# SM_Balam_22.net
KiCad netlist of a schematic drawn in Altium Designer
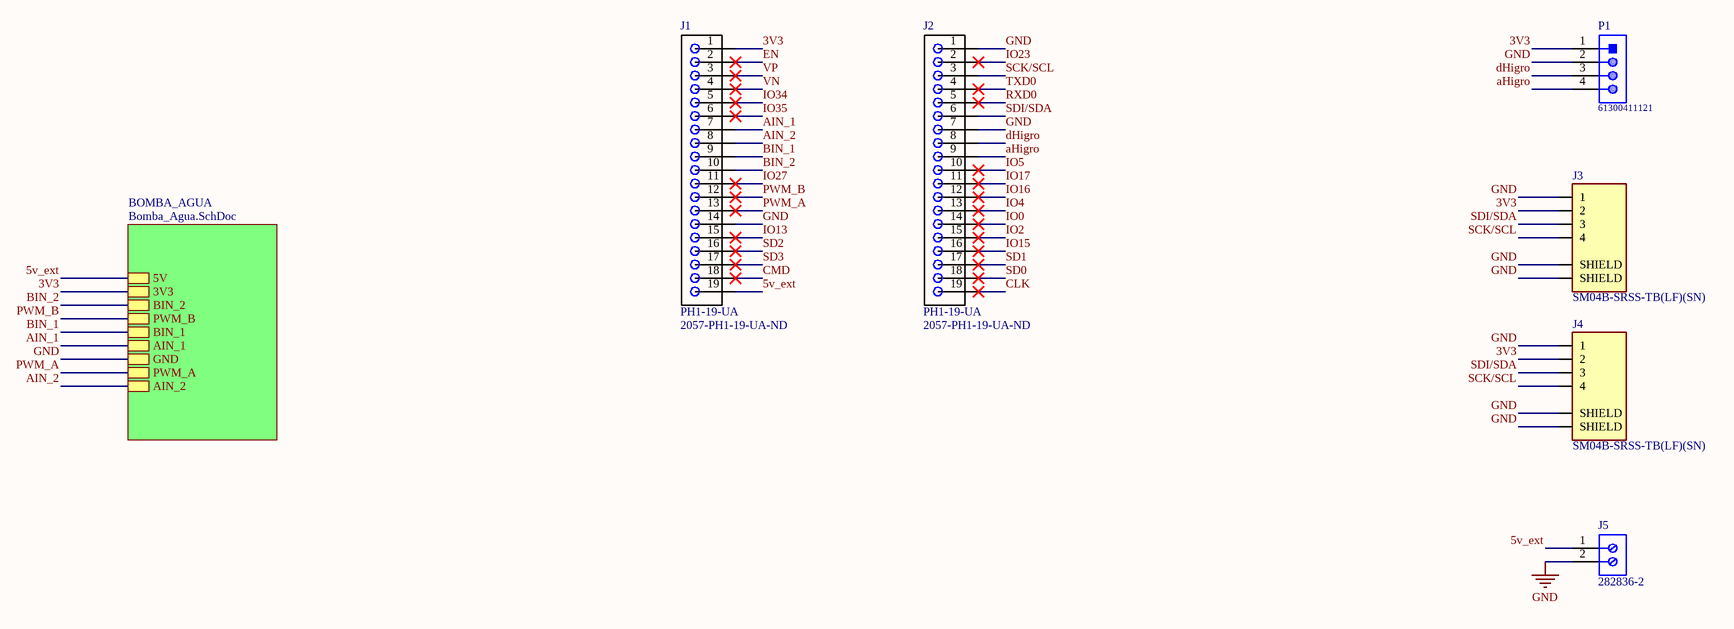
[diagram p0: SM_Balam_22.SchDoc]

(export (version "E")
  (design (tool "Eeschema 10.0.6"))
  (components
    (comp (ref "J1")
      (value "PH1-19-UA")
      (footprint "PH1-19-UA - Socket")
      (description "Connector Header Through Hole 19 position 0.100\" (2.54mm)")
      (fields (field (name "SUPPLIER PART NUMBER 1") "2057-PH1-19-UA-ND"))
      (libsource (lib "Isidro_Library") (part "PH1-19-UA"))
    )
    (comp (ref "J2")
      (value "PH1-19-UA")
      (footprint "PH1-19-UA - Socket")
      (description "Connector Header Through Hole 19 position 0.100\" (2.54mm)")
      (fields (field (name "SUPPLIER PART NUMBER 1") "2057-PH1-19-UA-ND"))
      (libsource (lib "Isidro_Library") (part "PH1-19-UA"))
    )
    (comp (ref "J3")
      (value "SM04B-SRSS-TB(LF)(SN)")
      (footprint "JST_SM04B-SRSS-TB(LF)(SN)")
      (description "Connector Header Surface Mount, Right Angle 4 position 0.039 _1.00mm_")
      (fields (field (name "MF") "JST Sales") (field (name "MP") "SM04B-SRSS-TB_LF__SN_"))
      (libsource (lib "AQIMon") (part "SM04B-SRSS-TB(LF)(SN)"))
    )
    (comp (ref "J4")
      (value "SM04B-SRSS-TB(LF)(SN)")
      (footprint "JST_SM04B-SRSS-TB(LF)(SN)")
      (description "Connector Header Surface Mount, Right Angle 4 position 0.039 _1.00mm_")
      (fields (field (name "MF") "JST Sales") (field (name "MP") "SM04B-SRSS-TB_LF__SN_"))
      (libsource (lib "AQIMon") (part "SM04B-SRSS-TB(LF)(SN)"))
    )
    (comp (ref "J5")
      (value "282836-2")
      (footprint "TECO-282836-2_V")
      (description "Female Header, Pitch 5 mm, 1 x 2 Position, Height 10 mm, Tail Length 3.5 mm, Rohs, Bulk")
      (fields (field (name "VOLTAGE") "300V") (field (name "MANUFACTURER") "TE Connectivity"))
      (libsource (lib "Altium Content Vault") (part "CN-1P-F-TB2"))
    )
    (comp (ref "P1")
      (value "61300411121")
      (footprint "61300411121")
      (description "THT Vertical Pin Header WR-PHD, Pitch 2.54 mm, Single Row, 4 pins")
      (fields (field (name "MANUFACTURER") "Wurth Elektronik") (field (name "PUBLISHER") "WurthElektronik"))
      (libsource (lib "Altium Content Vault") (part "WE-CN-1P-M-R4"))
    )
  )
  (nets
    (net (code "1") (name "/3V3") (class "Default")
      (node (ref "J1") (pin "1") (pinfunction "1_1") (pintype "passive"))
      (node (ref "J3") (pin "2") (pinfunction "2_2") (pintype "passive"))
      (node (ref "J4") (pin "2") (pinfunction "2_2") (pintype "passive"))
      (node (ref "P1") (pin "1") (pinfunction "1_1") (pintype "passive"))
    )
    (net (code "2") (name "/5v_ext") (class "Default")
      (node (ref "J1") (pin "19") (pinfunction "19_19") (pintype "passive"))
      (node (ref "J5") (pin "1") (pinfunction "1_1") (pintype "passive"))
    )
    (net (code "3") (name "/AIN_1") (class "Default")
      (node (ref "J1") (pin "7") (pinfunction "7_7") (pintype "passive"))
    )
    (net (code "4") (name "/AIN_2") (class "Default")
      (node (ref "J1") (pin "8") (pinfunction "8_8") (pintype "passive"))
    )
    (net (code "5") (name "/BIN_1") (class "Default")
      (node (ref "J1") (pin "9") (pinfunction "9_9") (pintype "passive"))
    )
    (net (code "6") (name "/BIN_2") (class "Default")
      (node (ref "J1") (pin "10") (pinfunction "10_10") (pintype "passive"))
    )
    (net (code "7") (name "/CLK") (class "Default")
      (node (ref "J2") (pin "19") (pinfunction "19_19") (pintype "passive+no_connect"))
    )
    (net (code "8") (name "/CMD") (class "Default")
      (node (ref "J1") (pin "18") (pinfunction "18_18") (pintype "passive+no_connect"))
    )
    (net (code "9") (name "/EN") (class "Default")
      (node (ref "J1") (pin "2") (pinfunction "2_2") (pintype "passive+no_connect"))
    )
    (net (code "10") (name "/IO0") (class "Default")
      (node (ref "J2") (pin "14") (pinfunction "14_14") (pintype "passive+no_connect"))
    )
    (net (code "11") (name "/IO2") (class "Default")
      (node (ref "J2") (pin "15") (pinfunction "15_15") (pintype "passive+no_connect"))
    )
    (net (code "12") (name "/IO4") (class "Default")
      (node (ref "J2") (pin "13") (pinfunction "13_13") (pintype "passive+no_connect"))
    )
    (net (code "13") (name "/IO5") (class "Default")
      (node (ref "J2") (pin "10") (pinfunction "10_10") (pintype "passive+no_connect"))
    )
    (net (code "14") (name "/IO13") (class "Default")
      (node (ref "J1") (pin "15") (pinfunction "15_15") (pintype "passive+no_connect"))
    )
    (net (code "15") (name "/IO15") (class "Default")
      (node (ref "J2") (pin "16") (pinfunction "16_16") (pintype "passive+no_connect"))
    )
    (net (code "16") (name "/IO16") (class "Default")
      (node (ref "J2") (pin "12") (pinfunction "12_12") (pintype "passive+no_connect"))
    )
    (net (code "17") (name "/IO17") (class "Default")
      (node (ref "J2") (pin "11") (pinfunction "11_11") (pintype "passive+no_connect"))
    )
    (net (code "18") (name "/IO23") (class "Default")
      (node (ref "J2") (pin "2") (pinfunction "2_2") (pintype "passive+no_connect"))
    )
    (net (code "19") (name "/IO27") (class "Default")
      (node (ref "J1") (pin "11") (pinfunction "11_11") (pintype "passive+no_connect"))
    )
    (net (code "20") (name "/IO34") (class "Default")
      (node (ref "J1") (pin "5") (pinfunction "5_5") (pintype "passive+no_connect"))
    )
    (net (code "21") (name "/IO35") (class "Default")
      (node (ref "J1") (pin "6") (pinfunction "6_6") (pintype "passive+no_connect"))
    )
    (net (code "22") (name "/PWM_A") (class "Default")
      (node (ref "J1") (pin "13") (pinfunction "13_13") (pintype "passive+no_connect"))
    )
    (net (code "23") (name "/PWM_B") (class "Default")
      (node (ref "J1") (pin "12") (pinfunction "12_12") (pintype "passive+no_connect"))
    )
    (net (code "24") (name "/RXD0") (class "Default")
      (node (ref "J2") (pin "5") (pinfunction "5_5") (pintype "passive+no_connect"))
    )
    (net (code "25") (name "/SCK{slash}SCL") (class "Default")
      (node (ref "J2") (pin "3") (pinfunction "3_3") (pintype "passive"))
      (node (ref "J3") (pin "4") (pinfunction "4_4") (pintype "passive"))
      (node (ref "J4") (pin "4") (pinfunction "4_4") (pintype "passive"))
    )
    (net (code "26") (name "/SD0") (class "Default")
      (node (ref "J2") (pin "18") (pinfunction "18_18") (pintype "passive+no_connect"))
    )
    (net (code "27") (name "/SD1") (class "Default")
      (node (ref "J2") (pin "17") (pinfunction "17_17") (pintype "passive+no_connect"))
    )
    (net (code "28") (name "/SD2") (class "Default")
      (node (ref "J1") (pin "16") (pinfunction "16_16") (pintype "passive+no_connect"))
    )
    (net (code "29") (name "/SD3") (class "Default")
      (node (ref "J1") (pin "17") (pinfunction "17_17") (pintype "passive+no_connect"))
    )
    (net (code "30") (name "/SDI{slash}SDA") (class "Default")
      (node (ref "J2") (pin "6") (pinfunction "6_6") (pintype "passive"))
      (node (ref "J3") (pin "3") (pinfunction "3_3") (pintype "passive"))
      (node (ref "J4") (pin "3") (pinfunction "3_3") (pintype "passive"))
    )
    (net (code "31") (name "/TXD0") (class "Default")
      (node (ref "J2") (pin "4") (pinfunction "4_4") (pintype "passive+no_connect"))
    )
    (net (code "32") (name "/VN") (class "Default")
      (node (ref "J1") (pin "4") (pinfunction "4_4") (pintype "passive+no_connect"))
    )
    (net (code "33") (name "/VP") (class "Default")
      (node (ref "J1") (pin "3") (pinfunction "3_3") (pintype "passive+no_connect"))
    )
    (net (code "34") (name "/aHigro") (class "Default")
      (node (ref "J2") (pin "9") (pinfunction "9_9") (pintype "passive"))
      (node (ref "P1") (pin "4") (pinfunction "4_4") (pintype "passive"))
    )
    (net (code "35") (name "/dHigro") (class "Default")
      (node (ref "J2") (pin "8") (pinfunction "8_8") (pintype "passive"))
      (node (ref "P1") (pin "3") (pinfunction "3_3") (pintype "passive"))
    )
    (net (code "36") (name "GND") (class "Default")
      (node (ref "J1") (pin "14") (pinfunction "14_14") (pintype "passive"))
      (node (ref "J2") (pin "1") (pinfunction "1_1") (pintype "passive"))
      (node (ref "J2") (pin "7") (pinfunction "7_7") (pintype "passive"))
      (node (ref "J3") (pin "1") (pinfunction "1_1") (pintype "passive"))
      (node (ref "J3") (pin "S1") (pinfunction "SHIELD_S1") (pintype "passive"))
      (node (ref "J3") (pin "S2") (pinfunction "SHIELD_S2") (pintype "passive"))
      (node (ref "J4") (pin "1") (pinfunction "1_1") (pintype "passive"))
      (node (ref "J4") (pin "S1") (pinfunction "SHIELD_S1") (pintype "passive"))
      (node (ref "J4") (pin "S2") (pinfunction "SHIELD_S2") (pintype "passive"))
      (node (ref "J5") (pin "2") (pinfunction "2_2") (pintype "passive"))
      (node (ref "P1") (pin "2") (pinfunction "2_2") (pintype "passive"))
    )
  )
)
